# srfnec-pcb.net
KiCad netlist of a schematic drawn in EAGLE
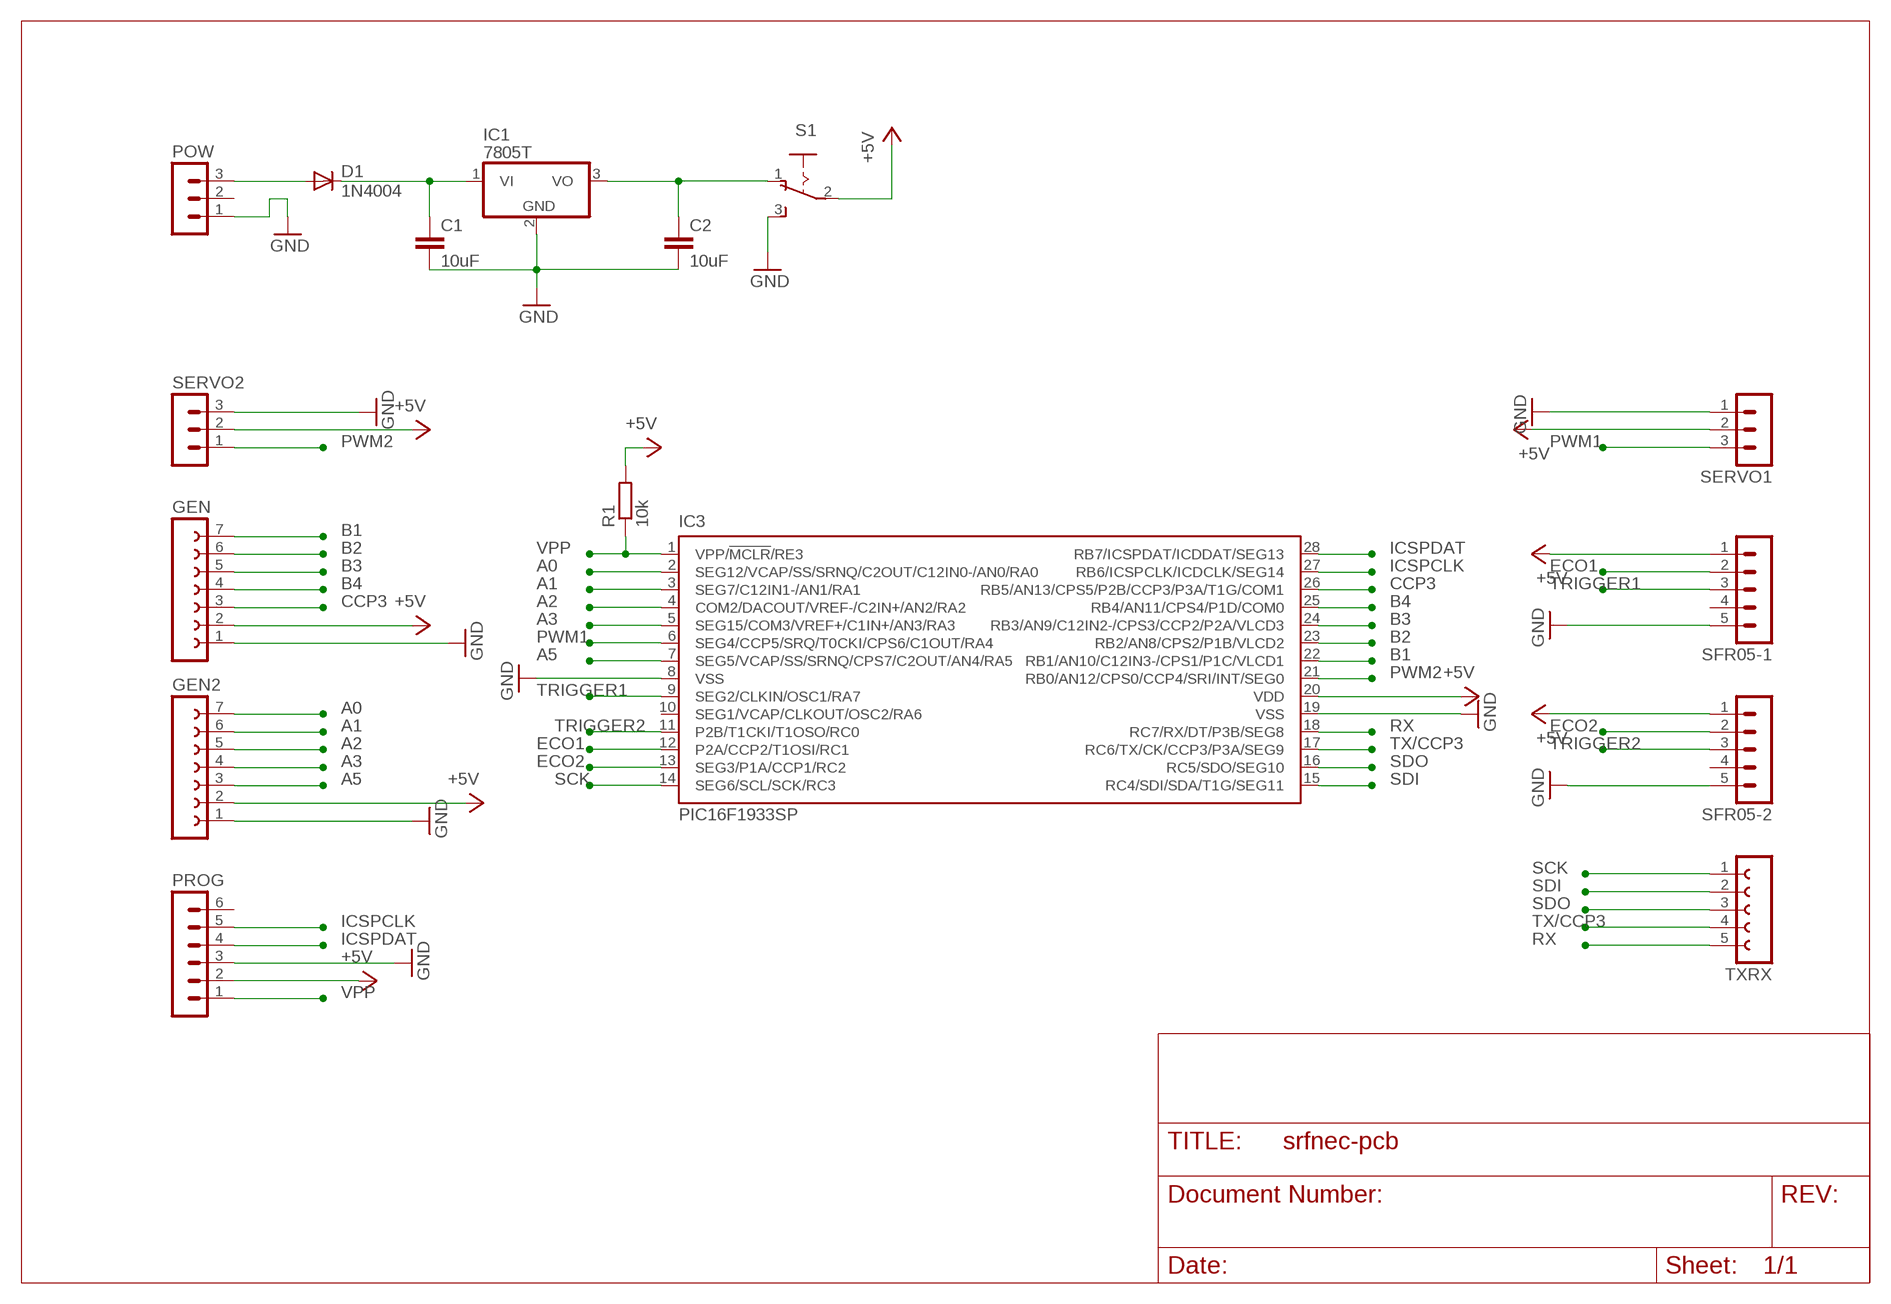
[diagram p0: schematic, sheet 1]

(export (version "E")
  (design (tool "Eeschema 10.0.6"))
  (components
    (comp (ref "C1")
      (value "10uF")
      (footprint "eagle-import:C5B2.5")
      (libsource (lib "eagle-import") (part "C5/2.5"))
    )
    (comp (ref "C2")
      (value "10uF")
      (footprint "eagle-import:C5B2.5")
      (libsource (lib "eagle-import") (part "C5/2.5"))
    )
    (comp (ref "D1")
      (value "1N4004")
      (footprint "eagle-import:DO41-10")
      (libsource (lib "eagle-import") (part "1N4004"))
    )
    (comp (ref "GEN")
      (value "FE07-1")
      (footprint "eagle-import:FE07")
      (libsource (lib "eagle-import") (part "FE07-1"))
    )
    (comp (ref "GEN2")
      (value "FE07-1")
      (footprint "eagle-import:FE07")
      (libsource (lib "eagle-import") (part "FE07-1"))
    )
    (comp (ref "IC1")
      (value "7805T")
      (footprint "eagle-import:TO220H")
      (libsource (lib "eagle-import") (part "78T05"))
    )
    (comp (ref "IC3")
      (value "PIC16F1933SP")
      (footprint "eagle-import:DIL28-3")
      (fields (field (name "MPN") "PIC16F1933-I/SP"))
      (libsource (lib "eagle-import") (part "PIC16F19SP33"))
    )
    (comp (ref "POW")
      (value "MA03-1")
      (footprint "eagle-import:MA03-1")
      (libsource (lib "eagle-import") (part "MA03-1"))
    )
    (comp (ref "PROG")
      (value "MA06-1")
      (footprint "eagle-import:MA06-1")
      (libsource (lib "eagle-import") (part "MA06-1"))
    )
    (comp (ref "R1")
      (value "10k")
      (footprint "eagle-import:0204_7")
      (libsource (lib "eagle-import") (part "R-EU_0204/7"))
    )
    (comp (ref "S1")
      (value "255SB")
      (footprint "eagle-import:255SB")
      (libsource (lib "eagle-import") (part "255SB"))
    )
    (comp (ref "SERVO1")
      (value "MA03-1")
      (footprint "eagle-import:MA03-1")
      (libsource (lib "eagle-import") (part "MA03-1"))
    )
    (comp (ref "SERVO2")
      (value "MA03-1")
      (footprint "eagle-import:MA03-1")
      (libsource (lib "eagle-import") (part "MA03-1"))
    )
    (comp (ref "SFR05-1")
      (value "MA05-1")
      (footprint "eagle-import:MA05-1")
      (libsource (lib "eagle-import") (part "MA05-1"))
    )
    (comp (ref "SFR05-2")
      (value "MA05-1")
      (footprint "eagle-import:MA05-1")
      (libsource (lib "eagle-import") (part "MA05-1"))
    )
    (comp (ref "TXRX")
      (value "FE05-1")
      (footprint "eagle-import:FE05-1")
      (libsource (lib "eagle-import") (part "FE05-1"))
    )
  )
  (nets
    (net (code "1") (name "+5V") (class "Default")
      (node (ref "GEN") (pin "2") (pinfunction "2_2") (pintype "passive"))
      (node (ref "GEN2") (pin "2") (pinfunction "2_2") (pintype "passive"))
      (node (ref "IC3") (pin "20") (pinfunction "VDD_20") (pintype "power_in"))
      (node (ref "PROG") (pin "2") (pinfunction "2_2") (pintype "passive"))
      (node (ref "R1") (pin "2") (pinfunction "2_2") (pintype "passive"))
      (node (ref "S1") (pin "2") (pinfunction "P_2") (pintype "passive"))
      (node (ref "SERVO1") (pin "2") (pinfunction "2_2") (pintype "passive"))
      (node (ref "SERVO2") (pin "2") (pinfunction "2_2") (pintype "passive"))
      (node (ref "SFR05-1") (pin "1") (pinfunction "1_1") (pintype "passive"))
      (node (ref "SFR05-2") (pin "1") (pinfunction "1_1") (pintype "passive"))
    )
    (net (code "2") (name "/A0") (class "Default")
      (node (ref "GEN2") (pin "7") (pinfunction "7_7") (pintype "passive"))
      (node (ref "IC3") (pin "2") (pinfunction "SEG12/VCAP/SS/SRNQ/C2OUT/C12IN0-/AN0/RA0_2") (pintype "bidirectional"))
    )
    (net (code "3") (name "/A1") (class "Default")
      (node (ref "GEN2") (pin "6") (pinfunction "6_6") (pintype "passive"))
      (node (ref "IC3") (pin "3") (pinfunction "SEG7/C12IN1-/AN1/RA1_3") (pintype "bidirectional"))
    )
    (net (code "4") (name "/A2") (class "Default")
      (node (ref "GEN2") (pin "5") (pinfunction "5_5") (pintype "passive"))
      (node (ref "IC3") (pin "4") (pinfunction "COM2/DACOUT/VREF-/C2IN+/AN2/RA2_4") (pintype "bidirectional"))
    )
    (net (code "5") (name "/A3") (class "Default")
      (node (ref "GEN2") (pin "4") (pinfunction "4_4") (pintype "passive"))
      (node (ref "IC3") (pin "5") (pinfunction "SEG15/COM3/VREF+/C1IN+/AN3/RA3_5") (pintype "bidirectional"))
    )
    (net (code "6") (name "/A5") (class "Default")
      (node (ref "GEN2") (pin "3") (pinfunction "3_3") (pintype "passive"))
      (node (ref "IC3") (pin "7") (pinfunction "SEG5/VCAP/SS/SRNQ/CPS7/C2OUT/AN4/RA5_7") (pintype "bidirectional"))
    )
    (net (code "7") (name "/B1") (class "Default")
      (node (ref "GEN") (pin "7") (pinfunction "7_7") (pintype "passive"))
      (node (ref "IC3") (pin "22") (pinfunction "RB1/AN10/C12IN3-/CPS1/P1C/VLCD1_22") (pintype "bidirectional"))
    )
    (net (code "8") (name "/B2") (class "Default")
      (node (ref "GEN") (pin "6") (pinfunction "6_6") (pintype "passive"))
      (node (ref "IC3") (pin "23") (pinfunction "RB2/AN8/CPS2/P1B/VLCD2_23") (pintype "bidirectional"))
    )
    (net (code "9") (name "/B3") (class "Default")
      (node (ref "GEN") (pin "5") (pinfunction "5_5") (pintype "passive"))
      (node (ref "IC3") (pin "24") (pinfunction "RB3/AN9/C12IN2-/CPS3/CCP2/P2A/VLCD3_24") (pintype "bidirectional"))
    )
    (net (code "10") (name "/B4") (class "Default")
      (node (ref "GEN") (pin "4") (pinfunction "4_4") (pintype "passive"))
      (node (ref "IC3") (pin "25") (pinfunction "RB4/AN11/CPS4/P1D/COM0_25") (pintype "bidirectional"))
    )
    (net (code "11") (name "/CCP3") (class "Default")
      (node (ref "GEN") (pin "3") (pinfunction "3_3") (pintype "passive"))
      (node (ref "IC3") (pin "26") (pinfunction "RB5/AN13/CPS5/P2B/CCP3/P3A/T1G/COM1_26") (pintype "bidirectional"))
    )
    (net (code "12") (name "/ECO1") (class "Default")
      (node (ref "IC3") (pin "12") (pinfunction "P2A/CCP2/T1OSI/RC1_12") (pintype "bidirectional"))
      (node (ref "SFR05-1") (pin "2") (pinfunction "2_2") (pintype "passive"))
    )
    (net (code "13") (name "/ECO2") (class "Default")
      (node (ref "IC3") (pin "13") (pinfunction "SEG3/P1A/CCP1/RC2_13") (pintype "bidirectional"))
      (node (ref "SFR05-2") (pin "2") (pinfunction "2_2") (pintype "passive"))
    )
    (net (code "14") (name "/ICSPCLK") (class "Default")
      (node (ref "IC3") (pin "27") (pinfunction "RB6/ICSPCLK/ICDCLK/SEG14_27") (pintype "bidirectional"))
      (node (ref "PROG") (pin "5") (pinfunction "5_5") (pintype "passive"))
    )
    (net (code "15") (name "/ICSPDAT") (class "Default")
      (node (ref "IC3") (pin "28") (pinfunction "RB7/ICSPDAT/ICDDAT/SEG13_28") (pintype "bidirectional"))
      (node (ref "PROG") (pin "4") (pinfunction "4_4") (pintype "passive"))
    )
    (net (code "16") (name "/PWM1") (class "Default")
      (node (ref "IC3") (pin "6") (pinfunction "SEG4/CCP5/SRQ/T0CKI/CPS6/C1OUT/RA4_6") (pintype "bidirectional"))
      (node (ref "SERVO1") (pin "3") (pinfunction "3_3") (pintype "passive"))
    )
    (net (code "17") (name "/PWM2") (class "Default")
      (node (ref "IC3") (pin "21") (pinfunction "RB0/AN12/CPS0/CCP4/SRI/INT/SEG0_21") (pintype "bidirectional"))
      (node (ref "SERVO2") (pin "1") (pinfunction "1_1") (pintype "passive"))
    )
    (net (code "18") (name "/RX") (class "Default")
      (node (ref "IC3") (pin "18") (pinfunction "RC7/RX/DT/P3B/SEG8_18") (pintype "bidirectional"))
      (node (ref "TXRX") (pin "5") (pinfunction "5_5") (pintype "passive"))
    )
    (net (code "19") (name "/SCK") (class "Default")
      (node (ref "IC3") (pin "14") (pinfunction "SEG6/SCL/SCK/RC3_14") (pintype "bidirectional"))
      (node (ref "TXRX") (pin "1") (pinfunction "1_1") (pintype "passive"))
    )
    (net (code "20") (name "/SDI") (class "Default")
      (node (ref "IC3") (pin "15") (pinfunction "RC4/SDI/SDA/T1G/SEG11_15") (pintype "bidirectional"))
      (node (ref "TXRX") (pin "2") (pinfunction "2_2") (pintype "passive"))
    )
    (net (code "21") (name "/SDO") (class "Default")
      (node (ref "IC3") (pin "16") (pinfunction "RC5/SDO/SEG10_16") (pintype "bidirectional"))
      (node (ref "TXRX") (pin "3") (pinfunction "3_3") (pintype "passive"))
    )
    (net (code "22") (name "/TRIGGER1") (class "Default")
      (node (ref "IC3") (pin "9") (pinfunction "SEG2/CLKIN/OSC1/RA7_9") (pintype "bidirectional"))
      (node (ref "SFR05-1") (pin "3") (pinfunction "3_3") (pintype "passive"))
    )
    (net (code "23") (name "/TRIGGER2") (class "Default")
      (node (ref "IC3") (pin "11") (pinfunction "P2B/T1CKI/T1OSO/RC0_11") (pintype "bidirectional"))
      (node (ref "SFR05-2") (pin "3") (pinfunction "3_3") (pintype "passive"))
    )
    (net (code "24") (name "/TX{slash}CCP3") (class "Default")
      (node (ref "IC3") (pin "17") (pinfunction "RC6/TX/CK/CCP3/P3A/SEG9_17") (pintype "bidirectional"))
      (node (ref "TXRX") (pin "4") (pinfunction "4_4") (pintype "passive"))
    )
    (net (code "25") (name "/VPP") (class "Default")
      (node (ref "IC3") (pin "1") (pinfunction "VPP/~{MCLR}/RE3_1") (pintype "input"))
      (node (ref "PROG") (pin "1") (pinfunction "1_1") (pintype "passive"))
      (node (ref "R1") (pin "1") (pinfunction "1_1") (pintype "passive"))
    )
    (net (code "26") (name "GND") (class "Default")
      (node (ref "C1") (pin "2") (pinfunction "2_2") (pintype "passive"))
      (node (ref "C2") (pin "2") (pinfunction "2_2") (pintype "passive"))
      (node (ref "GEN") (pin "1") (pinfunction "1_1") (pintype "passive"))
      (node (ref "GEN2") (pin "1") (pinfunction "1_1") (pintype "passive"))
      (node (ref "IC1") (pin "2") (pinfunction "GND_2") (pintype "passive"))
      (node (ref "IC3") (pin "19") (pinfunction "VSS_19") (pintype "power_in"))
      (node (ref "IC3") (pin "8") (pinfunction "VSS_8") (pintype "power_in"))
      (node (ref "POW") (pin "1") (pinfunction "1_1") (pintype "passive"))
      (node (ref "PROG") (pin "3") (pinfunction "3_3") (pintype "passive"))
      (node (ref "S1") (pin "3") (pinfunction "S_3") (pintype "passive"))
      (node (ref "SERVO1") (pin "1") (pinfunction "1_1") (pintype "passive"))
      (node (ref "SERVO2") (pin "3") (pinfunction "3_3") (pintype "passive"))
      (node (ref "SFR05-1") (pin "5") (pinfunction "5_5") (pintype "passive"))
      (node (ref "SFR05-2") (pin "5") (pinfunction "5_5") (pintype "passive"))
    )
    (net (code "27") (name "Net-(D1-PadA)") (class "Default")
      (node (ref "D1") (pin "A") (pinfunction "A_A") (pintype "passive"))
      (node (ref "POW") (pin "3") (pinfunction "3_3") (pintype "passive"))
    )
    (net (code "28") (name "Net-(IC1-VI)") (class "Default")
      (node (ref "C1") (pin "1") (pinfunction "1_1") (pintype "passive"))
      (node (ref "D1") (pin "C") (pinfunction "C_C") (pintype "passive"))
      (node (ref "IC1") (pin "1") (pinfunction "VI_1") (pintype "input"))
    )
    (net (code "29") (name "Net-(IC1-VO)") (class "Default")
      (node (ref "C2") (pin "1") (pinfunction "1_1") (pintype "passive"))
      (node (ref "IC1") (pin "3") (pinfunction "VO_3") (pintype "passive"))
      (node (ref "S1") (pin "1") (pinfunction "O_1") (pintype "passive"))
    )
    (net (code "30") (name "unconnected-(IC3-SEG1{slash}VCAP{slash}CLKOUT{slash}OSC2{slash}RA6-Pad10)") (class "Default")
      (node (ref "IC3") (pin "10") (pinfunction "SEG1/VCAP/CLKOUT/OSC2/RA6_10") (pintype "bidirectional"))
    )
    (net (code "31") (name "unconnected-(POW-Pad2)") (class "Default")
      (node (ref "POW") (pin "2") (pinfunction "2_2") (pintype "passive"))
    )
    (net (code "32") (name "unconnected-(PROG-Pad6)") (class "Default")
      (node (ref "PROG") (pin "6") (pinfunction "6_6") (pintype "passive"))
    )
    (net (code "33") (name "unconnected-(SFR05-1-Pad4)") (class "Default")
      (node (ref "SFR05-1") (pin "4") (pinfunction "4_4") (pintype "passive"))
    )
    (net (code "34") (name "unconnected-(SFR05-2-Pad4)") (class "Default")
      (node (ref "SFR05-2") (pin "4") (pinfunction "4_4") (pintype "passive"))
    )
  )
)
